# CC3D_V2.net
KiCad netlist of a schematic drawn in Altium Designer
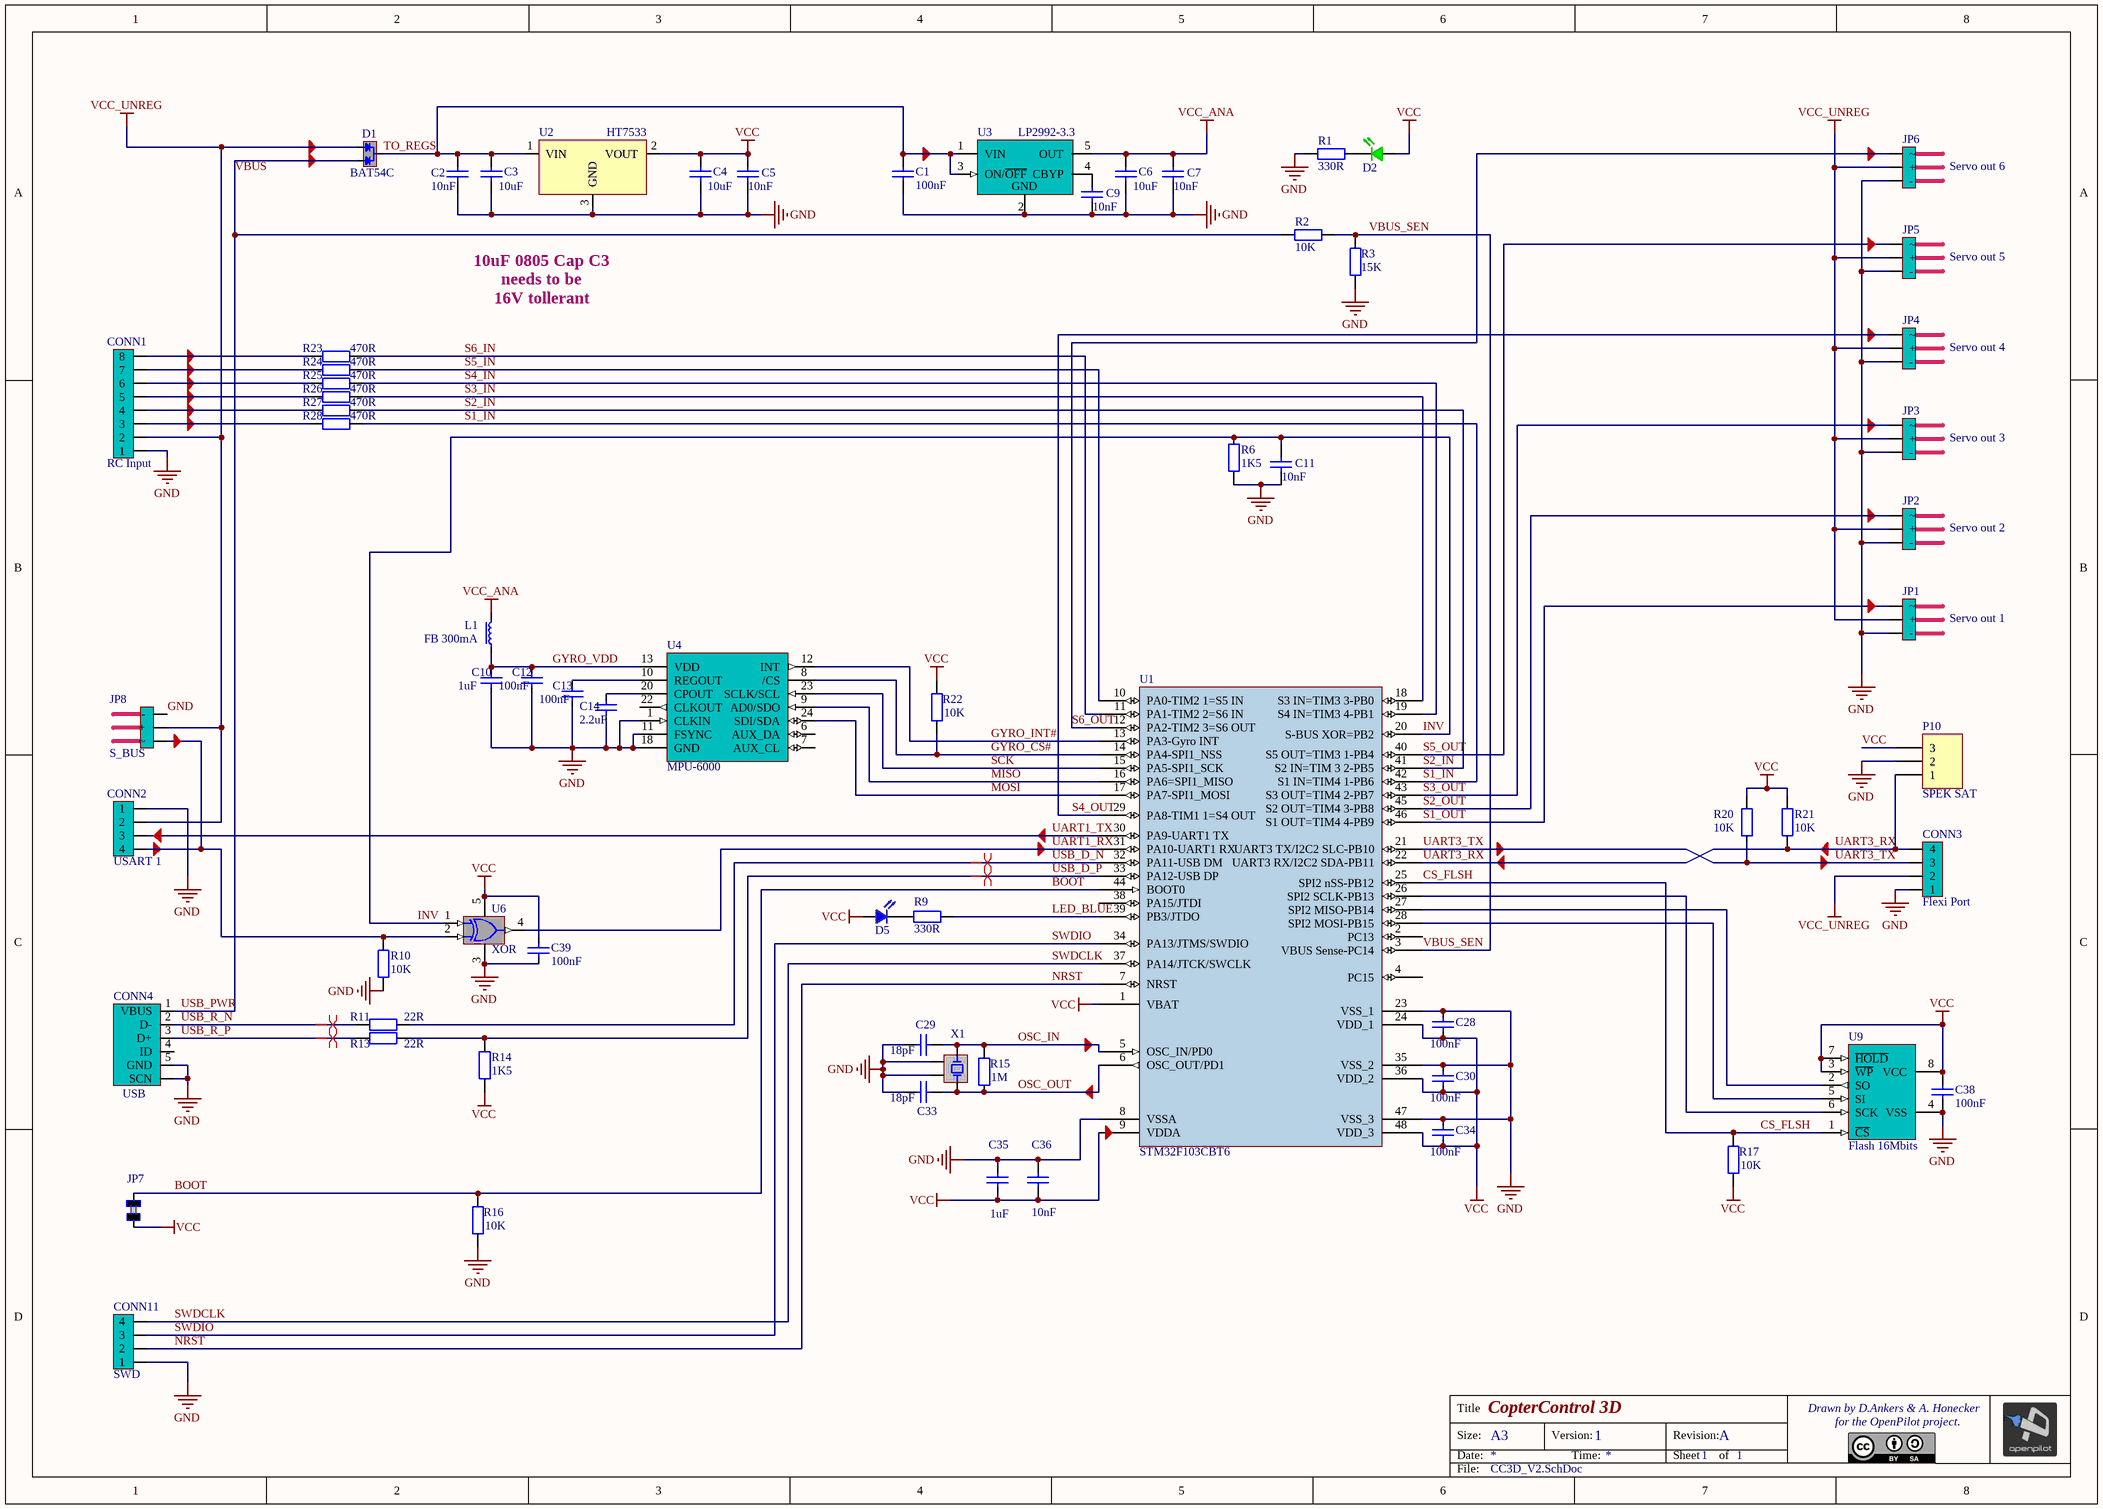
[diagram p0: CC3D_V2.SchDoc]

(export (version "E")
  (design (tool "Eeschema 10.0.6"))
  (components
    (comp (ref "C1")
      (value "100nF")
      (footprint "CAP603N")
      (description "Capacitor SMD")
      (fields (field (name "Comment") "Cap603") (field (name "PUBLISHER") "The OpenPilot Project"))
      (libsource (lib "") (part "Cap603_1"))
    )
    (comp (ref "C2")
      (value "10nF")
      (footprint "CAP603L")
      (description "Capacitor SMD")
      (fields (field (name "Comment") "Cap603") (field (name "PUBLISHER") "The OpenPilot Project"))
      (libsource (lib "") (part "Cap603_1"))
    )
    (comp (ref "C3")
      (value "10uF")
      (footprint "CAP805L")
      (description "Capacitor SMD")
      (fields (field (name "Comment") "Cap805") (field (name "PUBLISHER") "The OpenPilot Project"))
      (libsource (lib "OpenPilot") (part "Cap805"))
    )
    (comp (ref "C4")
      (value "10uF")
      (footprint "CAP805L")
      (description "Capacitor SMD")
      (fields (field (name "Comment") "Cap805") (field (name "PUBLISHER") "The OpenPilot Project"))
      (libsource (lib "OpenPilot") (part "Cap805"))
    )
    (comp (ref "C5")
      (value "10nF")
      (footprint "CAP603N")
      (description "Capacitor SMD")
      (fields (field (name "Comment") "Cap603") (field (name "PUBLISHER") "The OpenPilot Project"))
      (libsource (lib "") (part "Cap603_1"))
    )
    (comp (ref "C6")
      (value "10uF")
      (footprint "CAP805L")
      (description "Capacitor SMD")
      (fields (field (name "Comment") "Cap805") (field (name "PUBLISHER") "The OpenPilot Project"))
      (libsource (lib "OpenPilot") (part "Cap805"))
    )
    (comp (ref "C7")
      (value "10nF")
      (footprint "CAP603N")
      (description "Capacitor SMD")
      (fields (field (name "Comment") "Cap603") (field (name "PUBLISHER") "The OpenPilot Project"))
      (libsource (lib "") (part "Cap603_1"))
    )
    (comp (ref "C9")
      (value "10nF")
      (footprint "CAP603N")
      (description "Capacitor SMD")
      (fields (field (name "Comment") "Cap603") (field (name "PUBLISHER") "The OpenPilot Project"))
      (libsource (lib "") (part "Cap603_1"))
    )
    (comp (ref "C10")
      (value "1uF")
      (footprint "CAP603L")
      (description "Capacitor SMD")
      (fields (field (name "Comment") "Cap603") (field (name "PUBLISHER") "The OpenPilot Project"))
      (libsource (lib "OpenPilot") (part "Cap603"))
    )
    (comp (ref "C11")
      (value "10nF")
      (footprint "CAP603N")
      (description "Capacitor SMD")
      (fields (field (name "Comment") "Cap603") (field (name "PUBLISHER") "The OpenPilot Project"))
      (libsource (lib "") (part "Cap603_1"))
    )
    (comp (ref "C12")
      (value "100nF")
      (footprint "CAP603L")
      (description "Capacitor SMD")
      (fields (field (name "Comment") "Cap603") (field (name "PUBLISHER") "The OpenPilot Project"))
      (libsource (lib "OpenPilot") (part "Cap603"))
    )
    (comp (ref "C13")
      (value "100nF")
      (footprint "CAP603L")
      (description "Capacitor SMD")
      (fields (field (name "Comment") "Cap603") (field (name "PUBLISHER") "The OpenPilot Project"))
      (libsource (lib "OpenPilot") (part "Cap603"))
    )
    (comp (ref "C14")
      (value "2.2uF")
      (footprint "CAP603L")
      (description "Capacitor SMD")
      (fields (field (name "Comment") "Cap603") (field (name "PUBLISHER") "The OpenPilot Project"))
      (libsource (lib "OpenPilot") (part "Cap603"))
    )
    (comp (ref "C28")
      (value "100nF")
      (footprint "CAP603N")
      (description "Capacitor SMD")
      (fields (field (name "Comment") "Cap603") (field (name "PUBLISHER") "The OpenPilot Project"))
      (libsource (lib "OpenPilot") (part "Cap603"))
    )
    (comp (ref "C29")
      (value "18pF")
      (footprint "CAP603N")
      (description "Capacitor SMD")
      (fields (field (name "Comment") "Cap603") (field (name "PUBLISHER") "The OpenPilot Project"))
      (libsource (lib "") (part "Cap603_1"))
    )
    (comp (ref "C30")
      (value "100nF")
      (footprint "CAP603N")
      (description "Capacitor SMD")
      (fields (field (name "Comment") "Cap603") (field (name "PUBLISHER") "The OpenPilot Project"))
      (libsource (lib "OpenPilot") (part "Cap603"))
    )
    (comp (ref "C33")
      (value "18pF")
      (footprint "CAP603N")
      (description "Capacitor SMD")
      (fields (field (name "Comment") "Cap603") (field (name "PUBLISHER") "The OpenPilot Project"))
      (libsource (lib "") (part "Cap603_1"))
    )
    (comp (ref "C34")
      (value "100nF")
      (footprint "CAP603N")
      (description "Capacitor SMD")
      (fields (field (name "Comment") "Cap603") (field (name "PUBLISHER") "The OpenPilot Project"))
      (libsource (lib "OpenPilot") (part "Cap603"))
    )
    (comp (ref "C35")
      (value "1uF")
      (footprint "CAP603L")
      (description "Capacitor SMD")
      (fields (field (name "Comment") "Cap603") (field (name "PUBLISHER") "The OpenPilot Project"))
      (libsource (lib "OpenPilot") (part "Cap603"))
    )
    (comp (ref "C36")
      (value "10nF")
      (footprint "CAP603N")
      (description "Capacitor SMD")
      (fields (field (name "Comment") "Cap603") (field (name "PUBLISHER") "The OpenPilot Project"))
      (libsource (lib "") (part "Cap603_1"))
    )
    (comp (ref "C38")
      (value "100nF")
      (footprint "CAP603N")
      (description "Capacitor SMD")
      (fields (field (name "Comment") "Cap603") (field (name "PUBLISHER") "The OpenPilot Project"))
      (libsource (lib "") (part "Cap603_1"))
    )
    (comp (ref "C39")
      (value "100nF")
      (footprint "CAP603N")
      (description "Capacitor SMD")
      (fields (field (name "Comment") "Cap603") (field (name "PUBLISHER") "The OpenPilot Project"))
      (libsource (lib "OpenPilot") (part "Cap603"))
    )
    (comp (ref "CONN1")
      (value "RC Input")
      (footprint "JST SH 8 Pin Side Entry")
      (description "JST-SH 8-pin Side Entry Socket")
      (fields (field (name "MANUFACTURER") "Generic Components"))
      (libsource (lib "OpenPilot") (part "JST-SH 8-pin Side Entry Socket"))
    )
    (comp (ref "CONN2")
      (value "USART 1")
      (footprint "JST SH 4 Pin Side Entry")
      (description "JST-SH 4-pin Side Entry Socket")
      (fields (field (name "MANUFACTURER") "Generic Components"))
      (libsource (lib "") (part "JST-SH 4-pin Side Entry Socket_1"))
    )
    (comp (ref "CONN3")
      (value "Flexi Port")
      (footprint "JST SH 4 Pin Side Entry")
      (description "JST-SH 4-pin Side Entry Socket")
      (fields (field (name "MANUFACTURER") "Generic Components"))
      (libsource (lib "OpenPilot") (part "JST-SH 4-pin Side Entry Socket"))
    )
    (comp (ref "CONN4")
      (value "USB")
      (footprint "USB SMD")
      (description "USB Type-B SMT Socket")
      (libsource (lib "OpenPilot") (part "USB_SMT_B"))
    )
    (comp (ref "CONN11")
      (value "SWD")
      (footprint "JST SH 4 Pin Side Entry")
      (description "JST-SH 4-pin Side Entry Socket")
      (fields (field (name "MANUFACTURER") "Generic Components"))
      (libsource (lib "") (part "JST-SH 4-pin Side Entry Socket_2"))
    )
    (comp (ref "D1")
      (value "BAT54C")
      (footprint "SOT23-3N")
      (description "Dual Diode Command Cathode")
      (libsource (lib "OpenPilot") (part "BAT54C"))
    )
    (comp (ref "D2")
      (value "Green")
      (footprint "LED603N")
      (description "Green 603 LED")
      (libsource (lib "OpenPilot") (part "LED 603 Gr"))
    )
    (comp (ref "D5")
      (value "Blue")
      (footprint "LED603N")
      (description "Blue 603 LED")
      (libsource (lib "OpenPilot") (part "LED 603 Bl"))
    )
    (comp (ref "JP1")
      (value "Servo out 1")
      (footprint "SIP3 - 0.1")
      (description "Header, 3-Pin, 0.1\"")
      (fields (field (name "MANUFACTURER") "Generic Components"))
      (libsource (lib "OpenPilot") (part "Hdr 3 Pin 0.1"))
    )
    (comp (ref "JP2")
      (value "Servo out 2")
      (footprint "SIP3 - 0.1")
      (description "Header, 3-Pin, 0.1\"")
      (fields (field (name "MANUFACTURER") "Generic Components"))
      (libsource (lib "OpenPilot") (part "Hdr 3 Pin 0.1"))
    )
    (comp (ref "JP3")
      (value "Servo out 3")
      (footprint "SIP3 - 0.1")
      (description "Header, 3-Pin, 0.1\"")
      (fields (field (name "MANUFACTURER") "Generic Components"))
      (libsource (lib "OpenPilot") (part "Hdr 3 Pin 0.1"))
    )
    (comp (ref "JP4")
      (value "Servo out 4")
      (footprint "SIP3 - 0.1")
      (description "Header, 3-Pin, 0.1\"")
      (fields (field (name "MANUFACTURER") "Generic Components"))
      (libsource (lib "OpenPilot") (part "Hdr 3 Pin 0.1"))
    )
    (comp (ref "JP5")
      (value "Servo out 5")
      (footprint "SIP3 - 0.1")
      (description "Header, 3-Pin, 0.1\"")
      (fields (field (name "MANUFACTURER") "Generic Components"))
      (libsource (lib "OpenPilot") (part "Hdr 3 Pin 0.1"))
    )
    (comp (ref "JP6")
      (value "Servo out 6")
      (footprint "SIP3 - 0.1")
      (description "Header, 3-Pin, 0.1\"")
      (fields (field (name "MANUFACTURER") "Generic Components"))
      (libsource (lib "OpenPilot") (part "Hdr 3 Pin 0.1"))
    )
    (comp (ref "JP7")
      (value "2 PAD Touch JMP")
      (footprint "TOUCH JMP 2PAD")
      (description "2 Pad Touch Jumper")
      (fields (field (name "PUBLISHER") "The OpenPilot Project"))
      (libsource (lib "OpenPilot") (part "2 PAD Touch JMP"))
    )
    (comp (ref "JP8")
      (value "S_BUS")
      (footprint "SIP3 - SMT")
      (description "Header, 3-Pin, 0.1\"")
      (fields (field (name "MANUFACTURER") "Generic Components"))
      (libsource (lib "") (part "Hdr 3 Pin 0.1_1"))
    )
    (comp (ref "L1")
      (value "FB 300mA")
      (footprint "IND603N")
      (description "Ferrite Bead 300mA")
      (fields (field (name "MANUFACTURER") "Generic Components"))
      (libsource (lib "OpenPilot") (part "FerriteBead_300mA"))
    )
    (comp (ref "P10")
      (value "SPEK SAT")
      (footprint "1.5*3_SMT")
      (description "Header, 3-Pin")
      (fields (field (name "PUBLISHER") "Altium Limited"))
      (libsource (lib "Miscellaneous Connectors") (part "Header 3"))
    )
    (comp (ref "R1")
      (value "330R")
      (footprint "RES603N")
      (description "Resistor SMD")
      (fields (field (name "Comment") "Res603") (field (name "PUBLISHER") "The OpenPilot Project"))
      (libsource (lib "") (part "Res603_3"))
    )
    (comp (ref "R2")
      (value "10K")
      (footprint "RES603N")
      (description "Resistor SMD")
      (fields (field (name "Comment") "Res603") (field (name "PUBLISHER") "The OpenPilot Project"))
      (libsource (lib "") (part "Res603_3"))
    )
    (comp (ref "R3")
      (value "15K")
      (footprint "RES603N")
      (description "Resistor SMD")
      (fields (field (name "Comment") "Res603") (field (name "PUBLISHER") "The OpenPilot Project"))
      (libsource (lib "") (part "Res603_2"))
    )
    (comp (ref "R6")
      (value "1K5")
      (footprint "RES603N")
      (description "Resistor SMD")
      (fields (field (name "Comment") "Res603") (field (name "PUBLISHER") "The OpenPilot Project"))
      (libsource (lib "") (part "Res603_1"))
    )
    (comp (ref "R9")
      (value "330R")
      (footprint "RES603N")
      (description "Resistor SMD")
      (fields (field (name "Comment") "Res603") (field (name "PUBLISHER") "The OpenPilot Project"))
      (libsource (lib "") (part "Res603_3"))
    )
    (comp (ref "R10")
      (value "10K")
      (footprint "RES603N")
      (description "Resistor SMD")
      (fields (field (name "Comment") "Res603") (field (name "PUBLISHER") "The OpenPilot Project"))
      (libsource (lib "") (part "Res603_2"))
    )
    (comp (ref "R11")
      (value "22R")
      (footprint "RES603N")
      (description "Resistor SMD")
      (fields (field (name "Comment") "Res603") (field (name "PUBLISHER") "The OpenPilot Project"))
      (libsource (lib "OpenPilot") (part "Res603"))
    )
    (comp (ref "R13")
      (value "22R")
      (footprint "RES603N")
      (description "Resistor SMD")
      (fields (field (name "Comment") "Res603") (field (name "PUBLISHER") "The OpenPilot Project"))
      (libsource (lib "OpenPilot") (part "Res603"))
    )
    (comp (ref "R14")
      (value "1K5")
      (footprint "RES603N")
      (description "Resistor SMD")
      (fields (field (name "Comment") "Res603") (field (name "PUBLISHER") "The OpenPilot Project"))
      (libsource (lib "") (part "Res603_2"))
    )
    (comp (ref "R15")
      (value "1M")
      (footprint "RES603N")
      (description "Resistor SMD")
      (fields (field (name "Comment") "Res603") (field (name "PUBLISHER") "The OpenPilot Project"))
      (libsource (lib "") (part "Res603_4"))
    )
    (comp (ref "R16")
      (value "10K")
      (footprint "RES603N")
      (description "Resistor SMD")
      (fields (field (name "Comment") "Res603") (field (name "PUBLISHER") "The OpenPilot Project"))
      (libsource (lib "") (part "Res603_2"))
    )
    (comp (ref "R17")
      (value "10K")
      (footprint "RES603N")
      (description "Resistor SMD")
      (fields (field (name "Comment") "Res603") (field (name "PUBLISHER") "The OpenPilot Project"))
      (libsource (lib "") (part "Res603_2"))
    )
    (comp (ref "R20")
      (value "10K")
      (footprint "RES603N")
      (description "Resistor SMD")
      (fields (field (name "Comment") "Res603") (field (name "PUBLISHER") "The OpenPilot Project"))
      (libsource (lib "") (part "Res603_4"))
    )
    (comp (ref "R21")
      (value "10K")
      (footprint "RES603N")
      (description "Resistor SMD")
      (fields (field (name "Comment") "Res603") (field (name "PUBLISHER") "The OpenPilot Project"))
      (libsource (lib "") (part "Res603_2"))
    )
    (comp (ref "R22")
      (value "10K")
      (footprint "RES603N")
      (description "Resistor SMD")
      (fields (field (name "Comment") "Res603") (field (name "PUBLISHER") "The OpenPilot Project"))
      (libsource (lib "") (part "Res603_2"))
    )
    (comp (ref "R23")
      (value "470R")
      (footprint "RES603N")
      (description "Resistor SMD")
      (fields (field (name "Comment") "Res603") (field (name "PUBLISHER") "The OpenPilot Project"))
      (libsource (lib "OpenPilot") (part "Res603"))
    )
    (comp (ref "R24")
      (value "470R")
      (footprint "RES603N")
      (description "Resistor SMD")
      (fields (field (name "Comment") "Res603") (field (name "PUBLISHER") "The OpenPilot Project"))
      (libsource (lib "OpenPilot") (part "Res603"))
    )
    (comp (ref "R25")
      (value "470R")
      (footprint "RES603N")
      (description "Resistor SMD")
      (fields (field (name "Comment") "Res603") (field (name "PUBLISHER") "The OpenPilot Project"))
      (libsource (lib "OpenPilot") (part "Res603"))
    )
    (comp (ref "R26")
      (value "470R")
      (footprint "RES603N")
      (description "Resistor SMD")
      (fields (field (name "Comment") "Res603") (field (name "PUBLISHER") "The OpenPilot Project"))
      (libsource (lib "OpenPilot") (part "Res603"))
    )
    (comp (ref "R27")
      (value "470R")
      (footprint "RES603N")
      (description "Resistor SMD")
      (fields (field (name "Comment") "Res603") (field (name "PUBLISHER") "The OpenPilot Project"))
      (libsource (lib "OpenPilot") (part "Res603"))
    )
    (comp (ref "R28")
      (value "470R")
      (footprint "RES603N")
      (description "Resistor SMD")
      (fields (field (name "Comment") "Res603") (field (name "PUBLISHER") "The OpenPilot Project"))
      (libsource (lib "OpenPilot") (part "Res603"))
    )
    (comp (ref "U1")
      (value "STM32F103CBT6")
      (footprint "STM32 48 Lead")
      (description "STM32 ARM-based 32-bit MCU with 128 Kbytes Flash, 48-pin LQFP, Industrial Temperature")
      (fields (field (name "PUBLISHER") "Altium Limited"))
      (libsource (lib "OpenPilot") (part "STM32F103CBT6"))
    )
    (comp (ref "U2")
      (value "HT7533")
      (footprint "SOT89")
      (libsource (lib "R_SCH_LIB_2012_02_05") (part "HT75xx"))
    )
    (comp (ref "U3")
      (value "LP2992-3.3")
      (footprint "SOT23-5L")
      (description "3.3V 250mA LDO Regulator")
      (fields
        (field (name "MANUFACTURER") "National Semiconductor")
        (field (name "MANUFACTURER PART NUMBER") "LP2992AIM5-3.3/NOPB")
      )
      (libsource (lib "OpenPilot") (part "LP2985-3.3"))
    )
    (comp (ref "U4")
      (value "MPU-6000")
      (footprint "IMU-3000")
      (description "Invensense MPU-3/6000,  3-axis Gyros & Accel on 6000")
      (fields (field (name "MANUFACTURER") "Invensense") (field (name "PUBLISHER") "The OpenPilot Project"))
      (libsource (lib "OpenPilot") (part "MPU-3/6000"))
    )
    (comp (ref "U6")
      (value "XOR")
      (footprint "DCK-5")
      (description "XOR Gate SN74LVC1G86DCKR")
      (libsource (lib "OpenPilot") (part "XOR SN74LVC1G86DCKR"))
    )
    (comp (ref "U9")
      (value "Flash 16Mbits")
      (footprint "SOIC8_N")
      (description "16Mbit SPI Flash Memory")
      (fields (field (name "PUBLISHER") "The OpenPilot Project"))
      (libsource (lib "OpenPilot") (part "Flash 16Mb 75MHZ 8SOIC"))
    )
    (comp (ref "X1")
      (value "8MHz")
      (footprint "XTAL ACT530SMX-4 Series")
      (description "Surface Mount Quartz Crystal, Digikey 535-9720-1-ND")
      (libsource (lib "OpenPilot") (part "XTAL ACT530SMX-4"))
    )
  )
  (nets
    (net (code "1") (name "/BOOT") (class "Default")
      (node (ref "JP7") (pin "1") (pinfunction "1_1") (pintype "passive"))
      (node (ref "R16") (pin "2") (pinfunction "2_2") (pintype "passive"))
      (node (ref "U1") (pin "44") (pinfunction "BOOT0_44") (pintype "input"))
    )
    (net (code "2") (name "/CS_FLSH") (class "Default")
      (node (ref "R17") (pin "2") (pinfunction "2_2") (pintype "passive"))
      (node (ref "U1") (pin "25") (pinfunction "SPI2_nSS-PB12_25") (pintype "bidirectional"))
      (node (ref "U9") (pin "1") (pinfunction "~{CS}_1") (pintype "input"))
    )
    (net (code "3") (name "/GYRO_CS#") (class "Default")
      (node (ref "R22") (pin "1") (pinfunction "1_1") (pintype "passive"))
      (node (ref "U1") (pin "14") (pinfunction "PA4-SPI1_NSS_14") (pintype "bidirectional"))
      (node (ref "U4") (pin "8") (pinfunction "/CS_8") (pintype "passive"))
    )
    (net (code "4") (name "/GYRO_INT#") (class "Default")
      (node (ref "U1") (pin "13") (pinfunction "PA3-Gyro_INT_13") (pintype "bidirectional"))
      (node (ref "U4") (pin "12") (pinfunction "INT_12") (pintype "output"))
    )
    (net (code "5") (name "/GYRO_VDD") (class "Default")
      (node (ref "C10") (pin "1") (pinfunction "1_1") (pintype "passive"))
      (node (ref "C12") (pin "1") (pinfunction "1_1") (pintype "passive"))
      (node (ref "L1") (pin "1") (pinfunction "1_1") (pintype "passive"))
      (node (ref "U4") (pin "13") (pinfunction "VDD_13") (pintype "power_in"))
    )
    (net (code "6") (name "/INV") (class "Default")
      (node (ref "C11") (pin "1") (pinfunction "1_1") (pintype "passive"))
      (node (ref "R6") (pin "2") (pinfunction "2_2") (pintype "passive"))
      (node (ref "U1") (pin "20") (pinfunction "S-BUS_XOR=PB2_20") (pintype "bidirectional"))
      (node (ref "U6") (pin "1") (pinfunction "A_1") (pintype "input"))
    )
    (net (code "7") (name "/LED_BLUE") (class "Default")
      (node (ref "R9") (pin "2") (pinfunction "2_2") (pintype "passive"))
      (node (ref "U1") (pin "39") (pinfunction "PB3/JTDO_39") (pintype "bidirectional"))
    )
    (net (code "8") (name "/MISO") (class "Default")
      (node (ref "U1") (pin "16") (pinfunction "PA6=SPI1_MISO_16") (pintype "bidirectional"))
      (node (ref "U4") (pin "9") (pinfunction "AD0/SDO_9") (pintype "input"))
    )
    (net (code "9") (name "/MOSI") (class "Default")
      (node (ref "U1") (pin "17") (pinfunction "PA7-SPI1_MOSI_17") (pintype "bidirectional"))
      (node (ref "U4") (pin "24") (pinfunction "SDI/SDA_24") (pintype "bidirectional"))
    )
    (net (code "10") (name "/NRST") (class "Default")
      (node (ref "CONN11") (pin "2") (pinfunction "2_2") (pintype "passive"))
      (node (ref "U1") (pin "7") (pinfunction "NRST_7") (pintype "bidirectional"))
    )
    (net (code "11") (name "/OSC_IN") (class "Default")
      (node (ref "C29") (pin "2") (pinfunction "2_2") (pintype "passive"))
      (node (ref "R15") (pin "2") (pinfunction "2_2") (pintype "passive"))
      (node (ref "U1") (pin "5") (pinfunction "OSC_IN/PD0_5") (pintype "input"))
      (node (ref "X1") (pin "3") (pinfunction "3_3") (pintype "passive"))
    )
    (net (code "12") (name "/OSC_OUT") (class "Default")
      (node (ref "C33") (pin "2") (pinfunction "2_2") (pintype "passive"))
      (node (ref "R15") (pin "1") (pinfunction "1_1") (pintype "passive"))
      (node (ref "U1") (pin "6") (pinfunction "OSC_OUT/PD1_6") (pintype "output"))
      (node (ref "X1") (pin "1") (pinfunction "1_1") (pintype "passive"))
    )
    (net (code "13") (name "/S1_IN") (class "Default")
      (node (ref "R28") (pin "1") (pinfunction "1_1") (pintype "passive"))
      (node (ref "U1") (pin "42") (pinfunction "S1_IN=TIM4_1-PB6_42") (pintype "bidirectional"))
    )
    (net (code "14") (name "/S1_OUT") (class "Default")
      (node (ref "JP1") (pin "1") (pinfunction "~_1") (pintype "passive"))
      (node (ref "U1") (pin "46") (pinfunction "S1_OUT=TIM4_4-PB9_46") (pintype "bidirectional"))
    )
    (net (code "15") (name "/S2_IN") (class "Default")
      (node (ref "R27") (pin "1") (pinfunction "1_1") (pintype "passive"))
      (node (ref "U1") (pin "41") (pinfunction "S2_IN=TIM_3_2-PB5_41") (pintype "bidirectional"))
    )
    (net (code "16") (name "/S2_OUT") (class "Default")
      (node (ref "JP2") (pin "1") (pinfunction "~_1") (pintype "passive"))
      (node (ref "U1") (pin "45") (pinfunction "S2_OUT=TIM4_3-PB8_45") (pintype "bidirectional"))
    )
    (net (code "17") (name "/S3_IN") (class "Default")
      (node (ref "R26") (pin "1") (pinfunction "1_1") (pintype "passive"))
      (node (ref "U1") (pin "18") (pinfunction "S3_IN=TIM3_3-PB0_18") (pintype "bidirectional"))
    )
    (net (code "18") (name "/S3_OUT") (class "Default")
      (node (ref "JP3") (pin "1") (pinfunction "~_1") (pintype "passive"))
      (node (ref "U1") (pin "43") (pinfunction "S3_OUT=TIM4_2-PB7_43") (pintype "bidirectional"))
    )
    (net (code "19") (name "/S4_IN") (class "Default")
      (node (ref "R25") (pin "1") (pinfunction "1_1") (pintype "passive"))
      (node (ref "U1") (pin "19") (pinfunction "S4_IN=TIM3_4-PB1_19") (pintype "bidirectional"))
    )
    (net (code "20") (name "/S4_OUT") (class "Default")
      (node (ref "JP4") (pin "1") (pinfunction "~_1") (pintype "passive"))
      (node (ref "U1") (pin "29") (pinfunction "PA8-TIM1_1=S4_OUT_29") (pintype "bidirectional"))
    )
    (net (code "21") (name "/S5_IN") (class "Default")
      (node (ref "R24") (pin "1") (pinfunction "1_1") (pintype "passive"))
      (node (ref "U1") (pin "10") (pinfunction "PA0-TIM2_1=S5_IN_10") (pintype "bidirectional"))
    )
    (net (code "22") (name "/S5_OUT") (class "Default")
      (node (ref "JP5") (pin "1") (pinfunction "~_1") (pintype "passive"))
      (node (ref "U1") (pin "40") (pinfunction "S5_OUT=TIM3_1-PB4_40") (pintype "bidirectional"))
    )
    (net (code "23") (name "/S6_IN") (class "Default")
      (node (ref "R23") (pin "1") (pinfunction "1_1") (pintype "passive"))
      (node (ref "U1") (pin "11") (pinfunction "PA1-TIM2_2=S6_IN_11") (pintype "bidirectional"))
    )
    (net (code "24") (name "/S6_OUT") (class "Default")
      (node (ref "JP6") (pin "1") (pinfunction "~_1") (pintype "passive"))
      (node (ref "U1") (pin "12") (pinfunction "PA2-TIM2_3=S6_OUT_12") (pintype "bidirectional"))
    )
    (net (code "25") (name "/SCK") (class "Default")
      (node (ref "U1") (pin "15") (pinfunction "PA5-SPI1_SCK_15") (pintype "bidirectional"))
      (node (ref "U4") (pin "23") (pinfunction "SCLK/SCL_23") (pintype "input"))
    )
    (net (code "26") (name "/SWDCLK") (class "Default")
      (node (ref "CONN11") (pin "4") (pinfunction "4_4") (pintype "passive"))
      (node (ref "U1") (pin "37") (pinfunction "PA14/JTCK/SWCLK_37") (pintype "bidirectional"))
    )
    (net (code "27") (name "/SWDIO") (class "Default")
      (node (ref "CONN11") (pin "3") (pinfunction "3_3") (pintype "passive"))
      (node (ref "U1") (pin "34") (pinfunction "PA13/JTMS/SWDIO_34") (pintype "bidirectional"))
    )
    (net (code "28") (name "/TO_REGS") (class "Default")
      (node (ref "C1") (pin "1") (pinfunction "1_1") (pintype "passive"))
      (node (ref "C2") (pin "1") (pinfunction "1_1") (pintype "passive"))
      (node (ref "C3") (pin "1") (pinfunction "1_1") (pintype "passive"))
      (node (ref "D1") (pin "3") (pinfunction "COM_3") (pintype "passive"))
      (node (ref "U2") (pin "1") (pinfunction "VIN_1") (pintype "passive"))
      (node (ref "U3") (pin "1") (pinfunction "VIN_1") (pintype "power_in"))
      (node (ref "U3") (pin "3") (pinfunction "ON/~{OFF}_3") (pintype "input"))
    )
    (net (code "29") (name "/UART1_RX") (class "Default")
      (node (ref "U1") (pin "31") (pinfunction "PA10-UART1_RX_31") (pintype "bidirectional"))
      (node (ref "U6") (pin "4") (pinfunction "Y_4") (pintype "output"))
    )
    (net (code "30") (name "/UART1_TX") (class "Default")
      (node (ref "CONN2") (pin "3") (pinfunction "3_3") (pintype "passive"))
      (node (ref "U1") (pin "30") (pinfunction "PA9-UART1_TX_30") (pintype "bidirectional"))
    )
    (net (code "31") (name "/UART3_RX") (class "Default")
      (node (ref "CONN3") (pin "4") (pinfunction "4_4") (pintype "passive"))
      (node (ref "P10") (pin "1") (pinfunction "1_1") (pintype "passive"))
      (node (ref "R21") (pin "1") (pinfunction "1_1") (pintype "passive"))
      (node (ref "U1") (pin "22") (pinfunction "UART3_RX/I2C2_SDA-PB11_22") (pintype "bidirectional"))
    )
    (net (code "32") (name "/UART3_TX") (class "Default")
      (node (ref "CONN3") (pin "3") (pinfunction "3_3") (pintype "passive"))
      (node (ref "R20") (pin "1") (pinfunction "1_1") (pintype "passive"))
      (node (ref "U1") (pin "21") (pinfunction "UART3_TX/I2C2_SLC-PB10_21") (pintype "bidirectional"))
    )
    (net (code "33") (name "/USB_D_N") (class "Default")
      (node (ref "R11") (pin "1") (pinfunction "1_1") (pintype "passive"))
      (node (ref "U1") (pin "32") (pinfunction "PA11-USB_DM_32") (pintype "bidirectional"))
    )
    (net (code "34") (name "/USB_D_P") (class "Default")
      (node (ref "R13") (pin "1") (pinfunction "1_1") (pintype "passive"))
      (node (ref "R14") (pin "2") (pinfunction "2_2") (pintype "passive"))
      (node (ref "U1") (pin "33") (pinfunction "PA12-USB_DP_33") (pintype "bidirectional"))
    )
    (net (code "35") (name "/USB_PWR") (class "Default")
      (node (ref "CONN4") (pin "1") (pinfunction "VBUS_1") (pintype "passive"))
      (node (ref "D1") (pin "1") (pinfunction "A1_1") (pintype "passive"))
      (node (ref "R2") (pin "1") (pinfunction "1_1") (pintype "passive"))
    )
    (net (code "36") (name "/USB_R_N") (class "Default")
      (node (ref "CONN4") (pin "2") (pinfunction "D-_2") (pintype "passive"))
      (node (ref "R11") (pin "2") (pinfunction "2_2") (pintype "passive"))
    )
    (net (code "37") (name "/USB_R_P") (class "Default")
      (node (ref "CONN4") (pin "3") (pinfunction "D+_3") (pintype "passive"))
      (node (ref "R13") (pin "2") (pinfunction "2_2") (pintype "passive"))
    )
    (net (code "38") (name "/VBUS_SEN") (class "Default")
      (node (ref "R2") (pin "2") (pinfunction "2_2") (pintype "passive"))
      (node (ref "R3") (pin "2") (pinfunction "2_2") (pintype "passive"))
      (node (ref "U1") (pin "3") (pinfunction "VBUS_Sense-PC14_3") (pintype "bidirectional"))
    )
    (net (code "39") (name "GND") (class "Default")
      (node (ref "C1") (pin "2") (pinfunction "2_2") (pintype "passive"))
      (node (ref "C10") (pin "2") (pinfunction "2_2") (pintype "passive"))
      (node (ref "C11") (pin "2") (pinfunction "2_2") (pintype "passive"))
      (node (ref "C12") (pin "2") (pinfunction "2_2") (pintype "passive"))
      (node (ref "C13") (pin "2") (pinfunction "2_2") (pintype "passive"))
      (node (ref "C14") (pin "1") (pinfunction "1_1") (pintype "passive"))
      (node (ref "C2") (pin "2") (pinfunction "2_2") (pintype "passive"))
      (node (ref "C28") (pin "1") (pinfunction "1_1") (pintype "passive"))
      (node (ref "C29") (pin "1") (pinfunction "1_1") (pintype "passive"))
      (node (ref "C3") (pin "2") (pinfunction "2_2") (pintype "passive"))
      (node (ref "C30") (pin "1") (pinfunction "1_1") (pintype "passive"))
      (node (ref "C33") (pin "1") (pinfunction "1_1") (pintype "passive"))
      (node (ref "C34") (pin "1") (pinfunction "1_1") (pintype "passive"))
      (node (ref "C35") (pin "2") (pinfunction "2_2") (pintype "passive"))
      (node (ref "C36") (pin "1") (pinfunction "1_1") (pintype "passive"))
      (node (ref "C38") (pin "2") (pinfunction "2_2") (pintype "passive"))
      (node (ref "C39") (pin "2") (pinfunction "2_2") (pintype "passive"))
      (node (ref "C4") (pin "2") (pinfunction "2_2") (pintype "passive"))
      (node (ref "C5") (pin "2") (pinfunction "2_2") (pintype "passive"))
      (node (ref "C6") (pin "2") (pinfunction "2_2") (pintype "passive"))
      (node (ref "C7") (pin "2") (pinfunction "2_2") (pintype "passive"))
      (node (ref "C9") (pin "2") (pinfunction "2_2") (pintype "passive"))
      (node (ref "CONN1") (pin "1") (pinfunction "1_1") (pintype "passive"))
      (node (ref "CONN11") (pin "1") (pinfunction "1_1") (pintype "passive"))
      (node (ref "CONN2") (pin "1") (pinfunction "1_1") (pintype "passive"))
      (node (ref "CONN3") (pin "1") (pinfunction "1_1") (pintype "passive"))
      (node (ref "CONN4") (pin "0") (pinfunction "SCN_0") (pintype "passive"))
      (node (ref "CONN4") (pin "5") (pinfunction "GND_5") (pintype "passive"))
      (node (ref "JP1") (pin "3") (pinfunction "-_3") (pintype "passive"))
      (node (ref "JP2") (pin "3") (pinfunction "-_3") (pintype "passive"))
      (node (ref "JP3") (pin "3") (pinfunction "-_3") (pintype "passive"))
      (node (ref "JP4") (pin "3") (pinfunction "-_3") (pintype "passive"))
      (node (ref "JP5") (pin "3") (pinfunction "-_3") (pintype "passive"))
      (node (ref "JP6") (pin "3") (pinfunction "-_3") (pintype "passive"))
      (node (ref "JP8") (pin "3") (pinfunction "-_3") (pintype "passive"))
      (node (ref "P10") (pin "2") (pinfunction "2_2") (pintype "passive"))
      (node (ref "R1") (pin "1") (pinfunction "1_1") (pintype "passive"))
      (node (ref "R10") (pin "1") (pinfunction "1_1") (pintype "passive"))
      (node (ref "R16") (pin "1") (pinfunction "1_1") (pintype "passive"))
      (node (ref "R3") (pin "1") (pinfunction "1_1") (pintype "passive"))
      (node (ref "R6") (pin "1") (pinfunction "1_1") (pintype "passive"))
      (node (ref "U1") (pin "23") (pinfunction "VSS_1_23") (pintype "power_in"))
      (node (ref "U1") (pin "35") (pinfunction "VSS_2_35") (pintype "power_in"))
      (node (ref "U1") (pin "47") (pinfunction "VSS_3_47") (pintype "power_in"))
      (node (ref "U1") (pin "8") (pinfunction "VSSA_8") (pintype "power_in"))
      (node (ref "U2") (pin "3") (pinfunction "GND_3") (pintype "passive"))
      (node (ref "U3") (pin "2") (pinfunction "GND_2") (pintype "power_in"))
      (node (ref "U4") (pin "1") (pinfunction "CLKIN_1") (pintype "input"))
      (node (ref "U4") (pin "11") (pinfunction "FSYNC_11") (pintype "passive"))
      (node (ref "U4") (pin "18") (pinfunction "GND_18") (pintype "power_in"))
      (node (ref "U6") (pin "3") (pinfunction "GND_3") (pintype "power_in"))
      (node (ref "U9") (pin "4") (pinfunction "VSS_4") (pintype "power_in"))
      (node (ref "X1") (pin "2") (pinfunction "2_2") (pintype "passive"))
      (node (ref "X1") (pin "4") (pinfunction "4_4") (pintype "passive"))
    )
    (net (code "40") (name "Net-(CONN1-Pad3)") (class "Default")
      (node (ref "CONN1") (pin "3") (pinfunction "3_3") (pintype "passive"))
      (node (ref "R28") (pin "2") (pinfunction "2_2") (pintype "passive"))
    )
    (net (code "41") (name "Net-(CONN1-Pad4)") (class "Default")
      (node (ref "CONN1") (pin "4") (pinfunction "4_4") (pintype "passive"))
      (node (ref "R27") (pin "2") (pinfunction "2_2") (pintype "passive"))
    )
    (net (code "42") (name "Net-(CONN1-Pad5)") (class "Default")
      (node (ref "CONN1") (pin "5") (pinfunction "5_5") (pintype "passive"))
      (node (ref "R26") (pin "2") (pinfunction "2_2") (pintype "passive"))
    )
    (net (code "43") (name "Net-(CONN1-Pad6)") (class "Default")
      (node (ref "CONN1") (pin "6") (pinfunction "6_6") (pintype "passive"))
      (node (ref "R25") (pin "2") (pinfunction "2_2") (pintype "passive"))
    )
    (net (code "44") (name "Net-(CONN1-Pad7)") (class "Default")
      (node (ref "CONN1") (pin "7") (pinfunction "7_7") (pintype "passive"))
      (node (ref "R24") (pin "2") (pinfunction "2_2") (pintype "passive"))
    )
    (net (code "45") (name "Net-(CONN1-Pad8)") (class "Default")
      (node (ref "CONN1") (pin "8") (pinfunction "8_8") (pintype "passive"))
      (node (ref "R23") (pin "2") (pinfunction "2_2") (pintype "passive"))
    )
    (net (code "46") (name "Net-(D2-K)") (class "Default")
      (node (ref "D2") (pin "1") (pinfunction "K_1") (pintype "passive"))
      (node (ref "R1") (pin "2") (pinfunction "2_2") (pintype "passive"))
    )
    (net (code "47") (name "Net-(D5-K)") (class "Default")
      (node (ref "D5") (pin "1") (pinfunction "K_1") (pintype "passive"))
      (node (ref "R9") (pin "1") (pinfunction "1_1") (pintype "passive"))
    )
    (net (code "48") (name "Net-(JP8-~)") (class "Default")
      (node (ref "CONN2") (pin "4") (pinfunction "4_4") (pintype "passive"))
      (node (ref "JP8") (pin "1") (pinfunction "~_1") (pintype "passive"))
      (node (ref "R10") (pin "2") (pinfunction "2_2") (pintype "passive"))
      (node (ref "U6") (pin "2") (pinfunction "B_2") (pintype "input"))
    )
    (net (code "49") (name "Net-(U1-SPI2_MISO-PB14)") (class "Default")
      (node (ref "U1") (pin "27") (pinfunction "SPI2_MISO-PB14_27") (pintype "bidirectional"))
      (node (ref "U9") (pin "2") (pinfunction "SO_2") (pintype "output"))
    )
    (net (code "50") (name "Net-(U1-SPI2_MOSI-PB15)") (class "Default")
      (node (ref "U1") (pin "28") (pinfunction "SPI2_MOSI-PB15_28") (pintype "bidirectional"))
      (node (ref "U9") (pin "5") (pinfunction "SI_5") (pintype "input"))
    )
    (net (code "51") (name "Net-(U1-SPI2_SCLK-PB13)") (class "Default")
      (node (ref "U1") (pin "26") (pinfunction "SPI2_SCLK-PB13_26") (pintype "bidirectional"))
      (node (ref "U9") (pin "6") (pinfunction "SCK_6") (pintype "input"))
    )
    (net (code "52") (name "Net-(U3-CBYP)") (class "Default")
      (node (ref "C9") (pin "1") (pinfunction "1_1") (pintype "passive"))
      (node (ref "U3") (pin "4") (pinfunction "CBYP_4") (pintype "passive"))
    )
    (net (code "53") (name "Net-(U4-CPOUT)") (class "Default")
      (node (ref "C14") (pin "2") (pinfunction "2_2") (pintype "passive"))
      (node (ref "U4") (pin "20") (pinfunction "CPOUT_20") (pintype "passive"))
    )
    (net (code "54") (name "Net-(U4-REGOUT)") (class "Default")
      (node (ref "C13") (pin "1") (pinfunction "1_1") (pintype "passive"))
      (node (ref "U4") (pin "10") (pinfunction "REGOUT_10") (pintype "passive"))
    )
    (net (code "55") (name "VCC") (class "Default")
      (node (ref "C28") (pin "2") (pinfunction "2_2") (pintype "passive"))
      (node (ref "C30") (pin "2") (pinfunction "2_2") (pintype "passive"))
      (node (ref "C34") (pin "2") (pinfunction "2_2") (pintype "passive"))
      (node (ref "C35") (pin "1") (pinfunction "1_1") (pintype "passive"))
      (node (ref "C36") (pin "2") (pinfunction "2_2") (pintype "passive"))
      (node (ref "C38") (pin "1") (pinfunction "1_1") (pintype "passive"))
      (node (ref "C39") (pin "1") (pinfunction "1_1") (pintype "passive"))
      (node (ref "C4") (pin "1") (pinfunction "1_1") (pintype "passive"))
      (node (ref "C5") (pin "1") (pinfunction "1_1") (pintype "passive"))
      (node (ref "D2") (pin "2") (pinfunction "A_2") (pintype "passive"))
      (node (ref "D5") (pin "2") (pinfunction "A_2") (pintype "passive"))
      (node (ref "JP7") (pin "2") (pinfunction "2_2") (pintype "passive"))
      (node (ref "P10") (pin "3") (pinfunction "3_3") (pintype "passive"))
      (node (ref "R14") (pin "1") (pinfunction "1_1") (pintype "passive"))
      (node (ref "R17") (pin "1") (pinfunction "1_1") (pintype "passive"))
      (node (ref "R20") (pin "2") (pinfunction "2_2") (pintype "passive"))
      (node (ref "R21") (pin "2") (pinfunction "2_2") (pintype "passive"))
      (node (ref "R22") (pin "2") (pinfunction "2_2") (pintype "passive"))
      (node (ref "U1") (pin "1") (pinfunction "VBAT_1") (pintype "power_in"))
      (node (ref "U1") (pin "24") (pinfunction "VDD_1_24") (pintype "power_in"))
      (node (ref "U1") (pin "36") (pinfunction "VDD_2_36") (pintype "power_in"))
      (node (ref "U1") (pin "48") (pinfunction "VDD_3_48") (pintype "power_in"))
      (node (ref "U1") (pin "9") (pinfunction "VDDA_9") (pintype "power_in"))
      (node (ref "U2") (pin "2") (pinfunction "VOUT_2") (pintype "passive"))
      (node (ref "U6") (pin "5") (pinfunction "VCC_5") (pintype "power_in"))
      (node (ref "U9") (pin "3") (pinfunction "~{WP}_3") (pintype "input"))
      (node (ref "U9") (pin "7") (pinfunction "~{HOLD}_7") (pintype "input"))
      (node (ref "U9") (pin "8") (pinfunction "VCC_8") (pintype "power_in"))
    )
    (net (code "56") (name "VCC_ANA") (class "Default")
      (node (ref "C6") (pin "1") (pinfunction "1_1") (pintype "passive"))
      (node (ref "C7") (pin "1") (pinfunction "1_1") (pintype "passive"))
      (node (ref "L1") (pin "2") (pinfunction "2_2") (pintype "passive"))
      (node (ref "U3") (pin "5") (pinfunction "OUT_5") (pintype "power_in"))
    )
    (net (code "57") (name "VCC_UNREG") (class "Default")
      (node (ref "CONN1") (pin "2") (pinfunction "2_2") (pintype "passive"))
      (node (ref "CONN2") (pin "2") (pinfunction "2_2") (pintype "passive"))
      (node (ref "CONN3") (pin "2") (pinfunction "2_2") (pintype "passive"))
      (node (ref "D1") (pin "2") (pinfunction "A2_2") (pintype "passive"))
      (node (ref "JP1") (pin "2") (pinfunction "+_2") (pintype "passive"))
      (node (ref "JP2") (pin "2") (pinfunction "+_2") (pintype "passive"))
      (node (ref "JP3") (pin "2") (pinfunction "+_2") (pintype "passive"))
      (node (ref "JP4") (pin "2") (pinfunction "+_2") (pintype "passive"))
      (node (ref "JP5") (pin "2") (pinfunction "+_2") (pintype "passive"))
      (node (ref "JP6") (pin "2") (pinfunction "+_2") (pintype "passive"))
      (node (ref "JP8") (pin "2") (pinfunction "+_2") (pintype "passive"))
    )
    (net (code "58") (name "unconnected-(CONN4-ID-Pad4)") (class "Default")
      (node (ref "CONN4") (pin "4") (pinfunction "ID_4") (pintype "passive"))
    )
    (net (code "59") (name "unconnected-(U1-PA15{slash}JTDI-Pad38)") (class "Default")
      (node (ref "U1") (pin "38") (pinfunction "PA15/JTDI_38") (pintype "bidirectional"))
    )
    (net (code "60") (name "unconnected-(U1-PC13-Pad2)") (class "Default")
      (node (ref "U1") (pin "2") (pinfunction "PC13_2") (pintype "bidirectional"))
    )
    (net (code "61") (name "unconnected-(U1-PC15-Pad4)") (class "Default")
      (node (ref "U1") (pin "4") (pinfunction "PC15_4") (pintype "bidirectional"))
    )
    (net (code "62") (name "unconnected-(U4-AUX_CL-Pad7)") (class "Default")
      (node (ref "U4") (pin "7") (pinfunction "AUX_CL_7") (pintype "bidirectional"))
    )
    (net (code "63") (name "unconnected-(U4-AUX_DA-Pad6)") (class "Default")
      (node (ref "U4") (pin "6") (pinfunction "AUX_DA_6") (pintype "bidirectional"))
    )
    (net (code "64") (name "unconnected-(U4-CLKOUT-Pad22)") (class "Default")
      (node (ref "U4") (pin "22") (pinfunction "CLKOUT_22") (pintype "output"))
    )
    (net (code "65") (name "unconnected-(U4-NC-Pad2)") (class "Default")
      (node (ref "U4") (pin "2") (pinfunction "NC_2") (pintype "tri_state"))
    )
    (net (code "66") (name "unconnected-(U4-NC-Pad3)") (class "Default")
      (node (ref "U4") (pin "3") (pinfunction "NC_3") (pintype "tri_state"))
    )
    (net (code "67") (name "unconnected-(U4-NC-Pad4)") (class "Default")
      (node (ref "U4") (pin "4") (pinfunction "NC_4") (pintype "tri_state"))
    )
    (net (code "68") (name "unconnected-(U4-NC-Pad5)") (class "Default")
      (node (ref "U4") (pin "5") (pinfunction "NC_5") (pintype "tri_state"))
    )
    (net (code "69") (name "unconnected-(U4-NC-Pad14)") (class "Default")
      (node (ref "U4") (pin "14") (pinfunction "NC_14") (pintype "bidirectional"))
    )
    (net (code "70") (name "unconnected-(U4-NC-Pad15)") (class "Default")
      (node (ref "U4") (pin "15") (pinfunction "NC_15") (pintype "tri_state"))
    )
    (net (code "71") (name "unconnected-(U4-NC-Pad16)") (class "Default")
      (node (ref "U4") (pin "16") (pinfunction "NC_16") (pintype "tri_state"))
    )
    (net (code "72") (name "unconnected-(U4-NC-Pad17)") (class "Default")
      (node (ref "U4") (pin "17") (pinfunction "NC_17") (pintype "tri_state"))
    )
    (net (code "73") (name "unconnected-(U4-RESV-Pad19)") (class "Default")
      (node (ref "U4") (pin "19") (pinfunction "RESV_19") (pintype "passive"))
    )
    (net (code "74") (name "unconnected-(U4-RESV-Pad21)") (class "Default")
      (node (ref "U4") (pin "21") (pinfunction "RESV_21") (pintype "passive"))
    )
  )
)
